# Earphone-4.net
KiCad netlist of a schematic drawn in Altium Designer
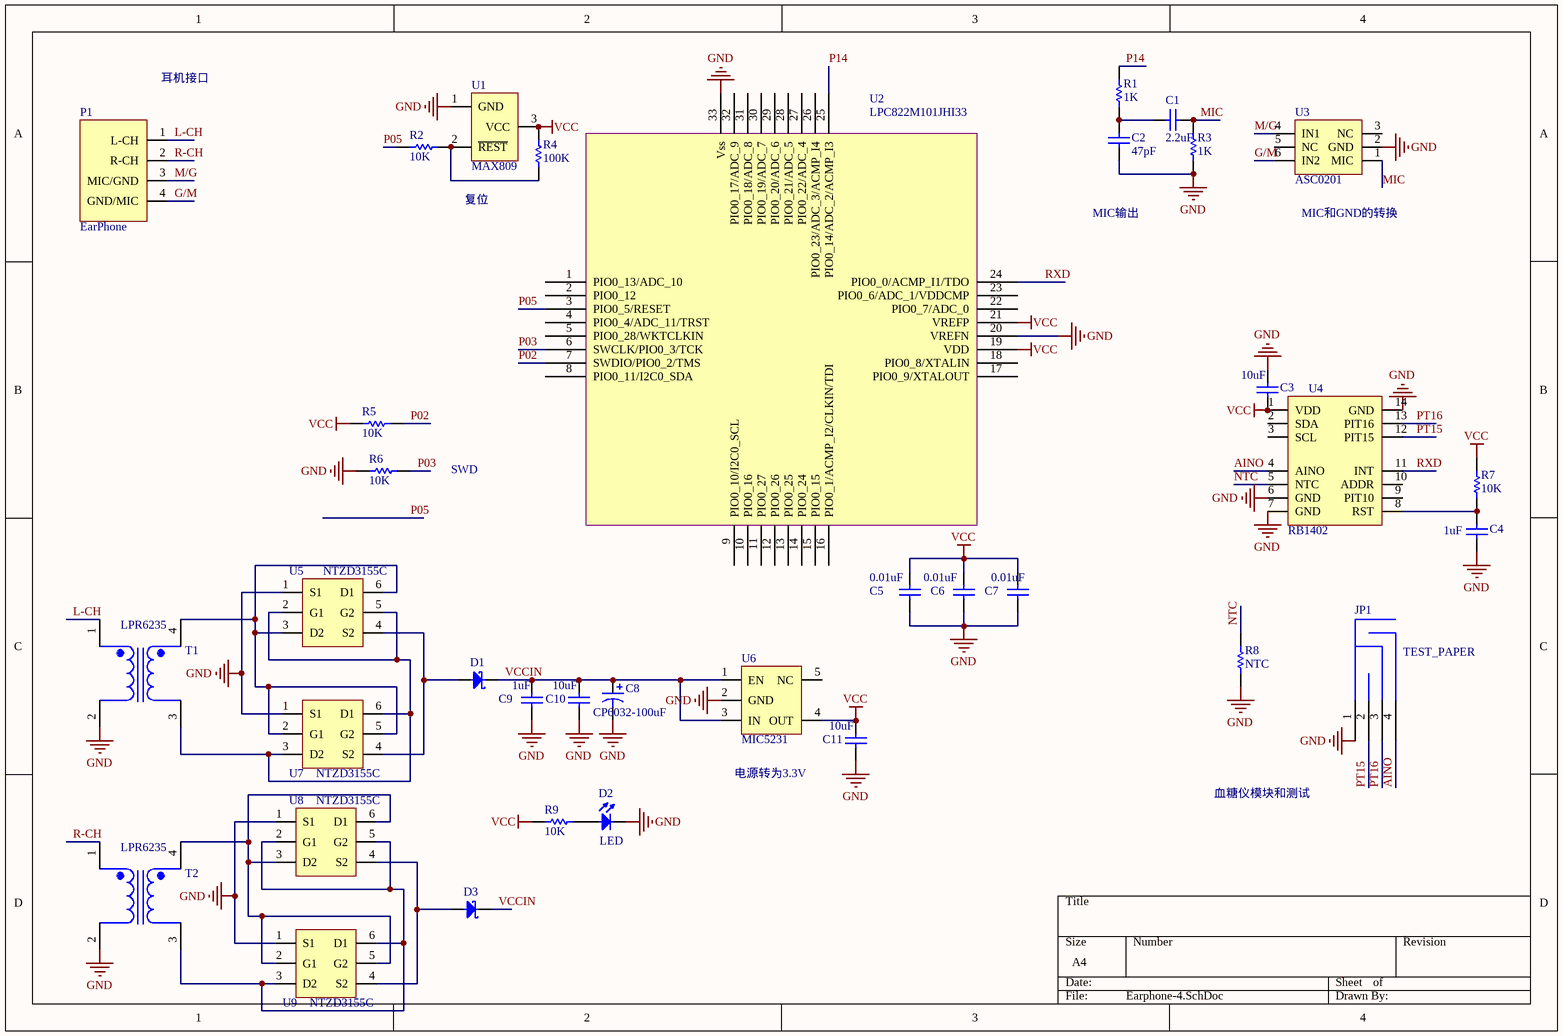
[diagram p0: Earphone-4.SchDoc]

(export (version "E")
  (design (tool "Eeschema 10.0.6"))
  (components
    (comp (ref "C1") (value "2.2uF") (footprint "0402C") (libsource (lib "Schlib1") (part "CAP")))
    (comp (ref "C2") (value "47pF") (footprint "0402C") (libsource (lib "Schlib1") (part "CAP")))
    (comp (ref "C3") (value "10uF") (footprint "0402C") (libsource (lib "Schlib1") (part "CAP")))
    (comp (ref "C4") (value "1uF") (footprint "0402C") (libsource (lib "Schlib1") (part "CAP")))
    (comp (ref "C5") (value "0.01uF") (footprint "0402C") (libsource (lib "Schlib1") (part "CAP")))
    (comp (ref "C6") (value "0.01uF") (footprint "0402C") (libsource (lib "Schlib1") (part "CAP")))
    (comp (ref "C7") (value "0.01uF") (footprint "0402C") (libsource (lib "Schlib1") (part "CAP")))
    (comp (ref "C8")
      (value "CP6032-100uF")
      (footprint "T3216-18[A]")
      (libsource (lib "Schlib1") (part "CAP POL2"))
    )
    (comp (ref "C9") (value "1uF") (footprint "0402C") (libsource (lib "Schlib1") (part "CAP")))
    (comp (ref "C10") (value "10uF") (footprint "0402C") (libsource (lib "Schlib1") (part "CAP")))
    (comp (ref "C11") (value "10uF") (footprint "0402C") (libsource (lib "Schlib1") (part "CAP")))
    (comp (ref "D1")
      (value "PMEG4002EJ")
      (footprint "SOD323")
      (description "SOD323F")
      (libsource (lib "Schlib1") (part "PMEG4002EJ"))
    )
    (comp (ref "D2") (value "LED") (footprint "0603L") (libsource (lib "Schlib1") (part "LED")))
    (comp (ref "D3")
      (value "PMEG4002EJ")
      (footprint "SOD323")
      (description "SOD323F")
      (libsource (lib "Schlib1") (part "PMEG4002EJ"))
    )
    (comp (ref "JP1")
      (value "TEST_PAPER")
      (footprint "TEST_PAPER")
      (libsource (lib "Schlib1") (part "TEST_PAPER"))
    )
    (comp (ref "P1") (value "EarPhone") (footprint "EarPhone") (libsource (lib "Schlib1") (part "EarPhone")))
    (comp (ref "R1") (value "1K") (footprint "0402R") (libsource (lib "Schlib1") (part "RES")))
    (comp (ref "R2") (value "10K") (footprint "0402R") (libsource (lib "Schlib1") (part "RES")))
    (comp (ref "R3") (value "1K") (footprint "0402R") (libsource (lib "Schlib1") (part "RES")))
    (comp (ref "R4") (value "100K") (footprint "0402R") (libsource (lib "Schlib1") (part "RES")))
    (comp (ref "R5") (value "10K") (footprint "0402R") (libsource (lib "Schlib1") (part "RES")))
    (comp (ref "R6") (value "10K") (footprint "0402R") (libsource (lib "Schlib1") (part "RES")))
    (comp (ref "R7") (value "10K") (footprint "0402R") (libsource (lib "Schlib1") (part "RES")))
    (comp (ref "R8") (value "NTC") (footprint "0603R") (libsource (lib "Schlib1") (part "RES")))
    (comp (ref "R9") (value "10K") (footprint "0402R") (libsource (lib "Schlib1") (part "RES")))
    (comp (ref "T1") (value "LPR6235") (footprint "Trans EMI") (libsource (lib "Schlib1") (part "Trans EMI")))
    (comp (ref "T2") (value "LPR6235") (footprint "Trans EMI") (libsource (lib "Schlib1") (part "Trans EMI")))
    (comp (ref "U1")
      (value "MAX809")
      (footprint "SOT23")
      (description "SOT23")
      (libsource (lib "Schlib1") (part "MAX809"))
    )
    (comp (ref "U2")
      (value "LPC822M101JHI33")
      (footprint "QFN50P500X500X100-33N")
      (libsource (lib "Schlib1") (part "LPC822M101JHI33"))
    )
    (comp (ref "U3")
      (value "ASC0201")
      (footprint "SOT23-6")
      (description "SOT23-6")
      (libsource (lib "Schlib1") (part "ASC0201"))
    )
    (comp (ref "U4") (value "RB1402") (footprint "RB1402") (libsource (lib "Schlib1") (part "RB1402")))
    (comp (ref "U5") (value "NTZD3155C") (footprint "SOT-563") (libsource (lib "Schlib1") (part "NTZD3155C")))
    (comp (ref "U6") (value "MIC5231") (footprint "SOT23-5") (libsource (lib "Schlib1") (part "MIC5231")))
    (comp (ref "U7") (value "NTZD3155C") (footprint "SOT-563") (libsource (lib "Schlib1") (part "NTZD3155C")))
    (comp (ref "U8") (value "NTZD3155C") (footprint "SOT-563") (libsource (lib "Schlib1") (part "NTZD3155C")))
    (comp (ref "U9") (value "NTZD3155C") (footprint "SOT-563") (libsource (lib "Schlib1") (part "NTZD3155C")))
  )
  (nets
    (net (code "1") (name "/AINO") (class "Default")
      (node (ref "JP1") (pin "4") (pinfunction "P_4") (pintype "passive"))
      (node (ref "U4") (pin "4") (pinfunction "AINO_4") (pintype "passive"))
    )
    (net (code "2") (name "/G{slash}M") (class "Default")
      (node (ref "P1") (pin "4") (pinfunction "GND/MIC_4") (pintype "passive"))
      (node (ref "U3") (pin "6") (pinfunction "IN2_6") (pintype "passive"))
    )
    (net (code "3") (name "/L-CH") (class "Default")
      (node (ref "P1") (pin "1") (pinfunction "L-CH_1") (pintype "passive"))
      (node (ref "T1") (pin "1") (pinfunction "1_1") (pintype "passive"))
    )
    (net (code "4") (name "/MIC") (class "Default")
      (node (ref "C1") (pin "1") (pinfunction "1_1") (pintype "passive"))
      (node (ref "R3") (pin "1") (pinfunction "1_1") (pintype "passive"))
      (node (ref "U3") (pin "1") (pinfunction "MIC_1") (pintype "passive"))
    )
    (net (code "5") (name "/M{slash}G") (class "Default")
      (node (ref "P1") (pin "3") (pinfunction "MIC/GND_3") (pintype "passive"))
      (node (ref "U3") (pin "4") (pinfunction "IN1_4") (pintype "passive"))
    )
    (net (code "6") (name "/NTC") (class "Default")
      (node (ref "R8") (pin "2") (pinfunction "2_2") (pintype "passive"))
      (node (ref "U4") (pin "5") (pinfunction "NTC_5") (pintype "passive"))
    )
    (net (code "7") (name "/P02") (class "Default")
      (node (ref "R5") (pin "2") (pinfunction "2_2") (pintype "passive"))
      (node (ref "U2") (pin "7") (pinfunction "SWDIO/PIO0_2/TMS_7") (pintype "passive"))
    )
    (net (code "8") (name "/P03") (class "Default")
      (node (ref "R6") (pin "1") (pinfunction "1_1") (pintype "passive"))
      (node (ref "U2") (pin "6") (pinfunction "SWCLK/PIO0_3/TCK_6") (pintype "passive"))
    )
    (net (code "9") (name "/P05") (class "Default")
      (node (ref "R2") (pin "1") (pinfunction "1_1") (pintype "passive"))
      (node (ref "U2") (pin "3") (pinfunction "PIO0_5/RESET_3") (pintype "passive"))
    )
    (net (code "10") (name "/P14") (class "Default")
      (node (ref "R1") (pin "1") (pinfunction "1_1") (pintype "passive"))
      (node (ref "U2") (pin "25") (pinfunction "PIO0_14/ADC_2/ACMP_I3_25") (pintype "passive"))
    )
    (net (code "11") (name "/PT15") (class "Default")
      (node (ref "JP1") (pin "2") (pinfunction "PC10_2") (pintype "passive"))
      (node (ref "U4") (pin "12") (pinfunction "PIT15_12") (pintype "passive"))
    )
    (net (code "12") (name "/PT16") (class "Default")
      (node (ref "JP1") (pin "3") (pinfunction "NOP_3") (pintype "passive"))
      (node (ref "U4") (pin "13") (pinfunction "PIT16_13") (pintype "passive"))
    )
    (net (code "13") (name "/R-CH") (class "Default")
      (node (ref "P1") (pin "2") (pinfunction "R-CH_2") (pintype "passive"))
      (node (ref "T2") (pin "1") (pinfunction "1_1") (pintype "passive"))
    )
    (net (code "14") (name "/RXD") (class "Default")
      (node (ref "U2") (pin "24") (pinfunction "PIO0_0/ACMP_I1/TDO_24") (pintype "passive"))
      (node (ref "U4") (pin "11") (pinfunction "INT_11") (pintype "passive"))
    )
    (net (code "15") (name "/VCCIN") (class "Default")
      (node (ref "C10") (pin "2") (pinfunction "2_2") (pintype "passive"))
      (node (ref "C8") (pin "1") (pinfunction "1_1") (pintype "passive"))
      (node (ref "C9") (pin "2") (pinfunction "2_2") (pintype "passive"))
      (node (ref "D1") (pin "1") (pinfunction "1_1") (pintype "passive"))
      (node (ref "D3") (pin "1") (pinfunction "1_1") (pintype "passive"))
      (node (ref "U6") (pin "1") (pinfunction "EN_1") (pintype "passive"))
      (node (ref "U6") (pin "3") (pinfunction "IN_3") (pintype "passive"))
    )
    (net (code "16") (name "GND") (class "Default")
      (node (ref "C10") (pin "1") (pinfunction "1_1") (pintype "passive"))
      (node (ref "C11") (pin "1") (pinfunction "1_1") (pintype "passive"))
      (node (ref "C2") (pin "1") (pinfunction "1_1") (pintype "passive"))
      (node (ref "C3") (pin "2") (pinfunction "2_2") (pintype "passive"))
      (node (ref "C4") (pin "1") (pinfunction "1_1") (pintype "passive"))
      (node (ref "C5") (pin "1") (pinfunction "1_1") (pintype "passive"))
      (node (ref "C6") (pin "1") (pinfunction "1_1") (pintype "passive"))
      (node (ref "C7") (pin "1") (pinfunction "1_1") (pintype "passive"))
      (node (ref "C8") (pin "2") (pinfunction "2_2") (pintype "passive"))
      (node (ref "C9") (pin "1") (pinfunction "1_1") (pintype "passive"))
      (node (ref "D2") (pin "2") (pinfunction "K_2") (pintype "passive"))
      (node (ref "JP1") (pin "1") (pinfunction "N_1") (pintype "passive"))
      (node (ref "R3") (pin "2") (pinfunction "2_2") (pintype "passive"))
      (node (ref "R6") (pin "2") (pinfunction "2_2") (pintype "passive"))
      (node (ref "R8") (pin "1") (pinfunction "1_1") (pintype "passive"))
      (node (ref "T1") (pin "2") (pinfunction "2_2") (pintype "passive"))
      (node (ref "T2") (pin "2") (pinfunction "2_2") (pintype "passive"))
      (node (ref "U1") (pin "1") (pinfunction "GND_1") (pintype "passive"))
      (node (ref "U2") (pin "20") (pinfunction "VREFN_20") (pintype "passive"))
      (node (ref "U2") (pin "33") (pinfunction "Vss_33") (pintype "passive"))
      (node (ref "U3") (pin "2") (pinfunction "GND_2") (pintype "passive"))
      (node (ref "U4") (pin "14") (pinfunction "GND_14") (pintype "passive"))
      (node (ref "U4") (pin "6") (pinfunction "GND_6") (pintype "passive"))
      (node (ref "U4") (pin "7") (pinfunction "GND_7") (pintype "passive"))
      (node (ref "U5") (pin "1") (pinfunction "S1_1") (pintype "passive"))
      (node (ref "U6") (pin "2") (pinfunction "GND_2") (pintype "passive"))
      (node (ref "U7") (pin "1") (pinfunction "S1_1") (pintype "passive"))
      (node (ref "U8") (pin "1") (pinfunction "S1_1") (pintype "passive"))
      (node (ref "U9") (pin "1") (pinfunction "S1_1") (pintype "passive"))
    )
    (net (code "17") (name "Net-(C1-Pad2)") (class "Default")
      (node (ref "C1") (pin "2") (pinfunction "2_2") (pintype "passive"))
      (node (ref "C2") (pin "2") (pinfunction "2_2") (pintype "passive"))
      (node (ref "R1") (pin "2") (pinfunction "2_2") (pintype "passive"))
    )
    (net (code "18") (name "Net-(D2-A)") (class "Default")
      (node (ref "D2") (pin "1") (pinfunction "A_1") (pintype "passive"))
      (node (ref "R9") (pin "2") (pinfunction "2_2") (pintype "passive"))
    )
    (net (code "19") (name "Net-(U1-~{REST})") (class "Default")
      (node (ref "R2") (pin "2") (pinfunction "2_2") (pintype "passive"))
      (node (ref "R4") (pin "1") (pinfunction "1_1") (pintype "passive"))
      (node (ref "U1") (pin "2") (pinfunction "~{REST}_2") (pintype "passive"))
    )
    (net (code "20") (name "Net-(U4-RST)") (class "Default")
      (node (ref "C4") (pin "2") (pinfunction "2_2") (pintype "passive"))
      (node (ref "R7") (pin "1") (pinfunction "1_1") (pintype "passive"))
      (node (ref "U4") (pin "8") (pinfunction "RST_8") (pintype "passive"))
    )
    (net (code "21") (name "Net-(U5-D1)") (class "Default")
      (node (ref "T1") (pin "4") (pinfunction "4_4") (pintype "passive"))
      (node (ref "U5") (pin "3") (pinfunction "D2_3") (pintype "passive"))
      (node (ref "U5") (pin "6") (pinfunction "D1_6") (pintype "passive"))
      (node (ref "U7") (pin "2") (pinfunction "G1_2") (pintype "passive"))
      (node (ref "U7") (pin "5") (pinfunction "G2_5") (pintype "passive"))
    )
    (net (code "22") (name "Net-(U5-G1)") (class "Default")
      (node (ref "T1") (pin "3") (pinfunction "3_3") (pintype "passive"))
      (node (ref "U5") (pin "2") (pinfunction "G1_2") (pintype "passive"))
      (node (ref "U5") (pin "5") (pinfunction "G2_5") (pintype "passive"))
      (node (ref "U7") (pin "3") (pinfunction "D2_3") (pintype "passive"))
      (node (ref "U7") (pin "6") (pinfunction "D1_6") (pintype "passive"))
    )
    (net (code "23") (name "Net-(U5-S2)") (class "Default")
      (node (ref "D1") (pin "2") (pinfunction "2_2") (pintype "passive"))
      (node (ref "U5") (pin "4") (pinfunction "S2_4") (pintype "passive"))
      (node (ref "U7") (pin "4") (pinfunction "S2_4") (pintype "passive"))
    )
    (net (code "24") (name "Net-(U8-D1)") (class "Default")
      (node (ref "T2") (pin "4") (pinfunction "4_4") (pintype "passive"))
      (node (ref "U8") (pin "3") (pinfunction "D2_3") (pintype "passive"))
      (node (ref "U8") (pin "6") (pinfunction "D1_6") (pintype "passive"))
      (node (ref "U9") (pin "2") (pinfunction "G1_2") (pintype "passive"))
      (node (ref "U9") (pin "5") (pinfunction "G2_5") (pintype "passive"))
    )
    (net (code "25") (name "Net-(U8-G1)") (class "Default")
      (node (ref "T2") (pin "3") (pinfunction "3_3") (pintype "passive"))
      (node (ref "U8") (pin "2") (pinfunction "G1_2") (pintype "passive"))
      (node (ref "U8") (pin "5") (pinfunction "G2_5") (pintype "passive"))
      (node (ref "U9") (pin "3") (pinfunction "D2_3") (pintype "passive"))
      (node (ref "U9") (pin "6") (pinfunction "D1_6") (pintype "passive"))
    )
    (net (code "26") (name "Net-(U8-S2)") (class "Default")
      (node (ref "D3") (pin "2") (pinfunction "2_2") (pintype "passive"))
      (node (ref "U8") (pin "4") (pinfunction "S2_4") (pintype "passive"))
      (node (ref "U9") (pin "4") (pinfunction "S2_4") (pintype "passive"))
    )
    (net (code "27") (name "VCC") (class "Default")
      (node (ref "C11") (pin "2") (pinfunction "2_2") (pintype "passive"))
      (node (ref "C3") (pin "1") (pinfunction "1_1") (pintype "passive"))
      (node (ref "C5") (pin "2") (pinfunction "2_2") (pintype "passive"))
      (node (ref "C6") (pin "2") (pinfunction "2_2") (pintype "passive"))
      (node (ref "C7") (pin "2") (pinfunction "2_2") (pintype "passive"))
      (node (ref "R4") (pin "2") (pinfunction "2_2") (pintype "passive"))
      (node (ref "R5") (pin "1") (pinfunction "1_1") (pintype "passive"))
      (node (ref "R7") (pin "2") (pinfunction "2_2") (pintype "passive"))
      (node (ref "R9") (pin "1") (pinfunction "1_1") (pintype "passive"))
      (node (ref "U1") (pin "3") (pinfunction "VCC_3") (pintype "passive"))
      (node (ref "U2") (pin "19") (pinfunction "VDD_19") (pintype "passive"))
      (node (ref "U2") (pin "21") (pinfunction "VREFP_21") (pintype "passive"))
      (node (ref "U4") (pin "1") (pinfunction "VDD_1") (pintype "passive"))
      (node (ref "U6") (pin "4") (pinfunction "OUT_4") (pintype "passive"))
    )
    (net (code "28") (name "unconnected-(U2-PIO0_1{slash}ACMP_I2{slash}CLKIN{slash}TDI-Pad16)") (class "Default")
      (node (ref "U2") (pin "16") (pinfunction "PIO0_1/ACMP_I2/CLKIN/TDI_16") (pintype "passive"))
    )
    (net (code "29") (name "unconnected-(U2-PIO0_4{slash}ADC_11{slash}TRST-Pad4)") (class "Default")
      (node (ref "U2") (pin "4") (pinfunction "PIO0_4/ADC_11/TRST_4") (pintype "passive"))
    )
    (net (code "30") (name "unconnected-(U2-PIO0_6{slash}ADC_1{slash}VDDCMP-Pad23)") (class "Default")
      (node (ref "U2") (pin "23") (pinfunction "PIO0_6/ADC_1/VDDCMP_23") (pintype "passive"))
    )
    (net (code "31") (name "unconnected-(U2-PIO0_7{slash}ADC_0-Pad22)") (class "Default")
      (node (ref "U2") (pin "22") (pinfunction "PIO0_7/ADC_0_22") (pintype "passive"))
    )
    (net (code "32") (name "unconnected-(U2-PIO0_8{slash}XTALIN-Pad18)") (class "Default")
      (node (ref "U2") (pin "18") (pinfunction "PIO0_8/XTALIN_18") (pintype "passive"))
    )
    (net (code "33") (name "unconnected-(U2-PIO0_9{slash}XTALOUT-Pad17)") (class "Default")
      (node (ref "U2") (pin "17") (pinfunction "PIO0_9/XTALOUT_17") (pintype "passive"))
    )
    (net (code "34") (name "unconnected-(U2-PIO0_10{slash}I2C0_SCL-Pad9)") (class "Default")
      (node (ref "U2") (pin "9") (pinfunction "PIO0_10/I2C0_SCL_9") (pintype "passive"))
    )
    (net (code "35") (name "unconnected-(U2-PIO0_11{slash}I2C0_SDA-Pad8)") (class "Default")
      (node (ref "U2") (pin "8") (pinfunction "PIO0_11/I2C0_SDA_8") (pintype "passive"))
    )
    (net (code "36") (name "unconnected-(U2-PIO0_12-Pad2)") (class "Default")
      (node (ref "U2") (pin "2") (pinfunction "PIO0_12_2") (pintype "passive"))
    )
    (net (code "37") (name "unconnected-(U2-PIO0_13{slash}ADC_10-Pad1)") (class "Default")
      (node (ref "U2") (pin "1") (pinfunction "PIO0_13/ADC_10_1") (pintype "passive"))
    )
    (net (code "38") (name "unconnected-(U2-PIO0_15-Pad15)") (class "Default")
      (node (ref "U2") (pin "15") (pinfunction "PIO0_15_15") (pintype "passive"))
    )
    (net (code "39") (name "unconnected-(U2-PIO0_16-Pad10)") (class "Default")
      (node (ref "U2") (pin "10") (pinfunction "PIO0_16_10") (pintype "passive"))
    )
    (net (code "40") (name "unconnected-(U2-PIO0_17{slash}ADC_9-Pad32)") (class "Default")
      (node (ref "U2") (pin "32") (pinfunction "PIO0_17/ADC_9_32") (pintype "passive"))
    )
    (net (code "41") (name "unconnected-(U2-PIO0_18{slash}ADC_8-Pad31)") (class "Default")
      (node (ref "U2") (pin "31") (pinfunction "PIO0_18/ADC_8_31") (pintype "passive"))
    )
    (net (code "42") (name "unconnected-(U2-PIO0_19{slash}ADC_7-Pad30)") (class "Default")
      (node (ref "U2") (pin "30") (pinfunction "PIO0_19/ADC_7_30") (pintype "passive"))
    )
    (net (code "43") (name "unconnected-(U2-PIO0_20{slash}ADC_6-Pad29)") (class "Default")
      (node (ref "U2") (pin "29") (pinfunction "PIO0_20/ADC_6_29") (pintype "passive"))
    )
    (net (code "44") (name "unconnected-(U2-PIO0_21{slash}ADC_5-Pad28)") (class "Default")
      (node (ref "U2") (pin "28") (pinfunction "PIO0_21/ADC_5_28") (pintype "passive"))
    )
    (net (code "45") (name "unconnected-(U2-PIO0_22{slash}ADC_4-Pad27)") (class "Default")
      (node (ref "U2") (pin "27") (pinfunction "PIO0_22/ADC_4_27") (pintype "passive"))
    )
    (net (code "46") (name "unconnected-(U2-PIO0_23{slash}ADC_3{slash}ACMP_I4-Pad26)") (class "Default")
      (node (ref "U2") (pin "26") (pinfunction "PIO0_23/ADC_3/ACMP_I4_26") (pintype "passive"))
    )
    (net (code "47") (name "unconnected-(U2-PIO0_24-Pad14)") (class "Default")
      (node (ref "U2") (pin "14") (pinfunction "PIO0_24_14") (pintype "passive"))
    )
    (net (code "48") (name "unconnected-(U2-PIO0_25-Pad13)") (class "Default")
      (node (ref "U2") (pin "13") (pinfunction "PIO0_25_13") (pintype "passive"))
    )
    (net (code "49") (name "unconnected-(U2-PIO0_26-Pad12)") (class "Default")
      (node (ref "U2") (pin "12") (pinfunction "PIO0_26_12") (pintype "passive"))
    )
    (net (code "50") (name "unconnected-(U2-PIO0_27-Pad11)") (class "Default")
      (node (ref "U2") (pin "11") (pinfunction "PIO0_27_11") (pintype "passive"))
    )
    (net (code "51") (name "unconnected-(U2-PIO0_28{slash}WKTCLKIN-Pad5)") (class "Default")
      (node (ref "U2") (pin "5") (pinfunction "PIO0_28/WKTCLKIN_5") (pintype "passive"))
    )
    (net (code "52") (name "unconnected-(U3-NC-Pad3)") (class "Default")
      (node (ref "U3") (pin "3") (pinfunction "NC_3") (pintype "passive"))
    )
    (net (code "53") (name "unconnected-(U3-NC-Pad5)") (class "Default")
      (node (ref "U3") (pin "5") (pinfunction "NC_5") (pintype "passive"))
    )
    (net (code "54") (name "unconnected-(U4-ADDR-Pad10)") (class "Default")
      (node (ref "U4") (pin "10") (pinfunction "ADDR_10") (pintype "passive"))
    )
    (net (code "55") (name "unconnected-(U4-PIT10-Pad9)") (class "Default")
      (node (ref "U4") (pin "9") (pinfunction "PIT10_9") (pintype "passive"))
    )
    (net (code "56") (name "unconnected-(U4-SCL-Pad3)") (class "Default")
      (node (ref "U4") (pin "3") (pinfunction "SCL_3") (pintype "passive"))
    )
    (net (code "57") (name "unconnected-(U4-SDA-Pad2)") (class "Default")
      (node (ref "U4") (pin "2") (pinfunction "SDA_2") (pintype "passive"))
    )
    (net (code "58") (name "unconnected-(U6-NC-Pad5)") (class "Default")
      (node (ref "U6") (pin "5") (pinfunction "NC_5") (pintype "passive"))
    )
  )
)
